# Smoother.net
KiCad netlist of a schematic drawn in EAGLE
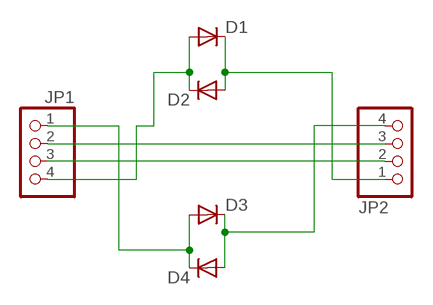
[diagram p0: schematic, sheet 1]

(export (version "E")
  (design (tool "Eeschema 10.0.6"))
  (components
    (comp (ref "D1")
      (value "DIODE_ES1J")
      (footprint "eagle-import:DO214AC")
      (libsource (lib "eagle-import") (part "DIODE_ES1J"))
    )
    (comp (ref "D2")
      (value "DIODE_ES1J")
      (footprint "eagle-import:DO214AC")
      (libsource (lib "eagle-import") (part "DIODE_ES1J"))
    )
    (comp (ref "D3")
      (value "DIODE_ES1J")
      (footprint "eagle-import:DO214AC")
      (libsource (lib "eagle-import") (part "DIODE_ES1J"))
    )
    (comp (ref "D4")
      (value "DIODE_ES1J")
      (footprint "eagle-import:DO214AC")
      (libsource (lib "eagle-import") (part "DIODE_ES1J"))
    )
    (comp (ref "JP1")
      (value "PINHD-1X4/90")
      (footprint "eagle-import:1X04_90")
      (libsource (lib "eagle-import") (part "PINHD-1X4/90"))
    )
    (comp (ref "JP2")
      (value "PINHD-1X4/90")
      (footprint "eagle-import:1X04_90")
      (libsource (lib "eagle-import") (part "PINHD-1X4/90"))
    )
  )
  (nets
    (net (code "1") (name "Net-(D1-PadA)") (class "Default")
      (node (ref "D1") (pin "A") (pinfunction "A_A") (pintype "passive"))
      (node (ref "D2") (pin "C") (pinfunction "C_C") (pintype "passive"))
      (node (ref "JP1") (pin "4") (pinfunction "4_4") (pintype "passive"))
    )
    (net (code "2") (name "Net-(D1-PadC)") (class "Default")
      (node (ref "D1") (pin "C") (pinfunction "C_C") (pintype "passive"))
      (node (ref "D2") (pin "A") (pinfunction "A_A") (pintype "passive"))
      (node (ref "JP2") (pin "1") (pinfunction "1_1") (pintype "passive"))
    )
    (net (code "3") (name "Net-(D3-PadA)") (class "Default")
      (node (ref "D3") (pin "A") (pinfunction "A_A") (pintype "passive"))
      (node (ref "D4") (pin "C") (pinfunction "C_C") (pintype "passive"))
      (node (ref "JP1") (pin "1") (pinfunction "1_1") (pintype "passive"))
    )
    (net (code "4") (name "Net-(D3-PadC)") (class "Default")
      (node (ref "D3") (pin "C") (pinfunction "C_C") (pintype "passive"))
      (node (ref "D4") (pin "A") (pinfunction "A_A") (pintype "passive"))
      (node (ref "JP2") (pin "4") (pinfunction "4_4") (pintype "passive"))
    )
    (net (code "5") (name "Net-(JP1-Pad2)") (class "Default")
      (node (ref "JP1") (pin "2") (pinfunction "2_2") (pintype "passive"))
      (node (ref "JP2") (pin "3") (pinfunction "3_3") (pintype "passive"))
    )
    (net (code "6") (name "Net-(JP1-Pad3)") (class "Default")
      (node (ref "JP1") (pin "3") (pinfunction "3_3") (pintype "passive"))
      (node (ref "JP2") (pin "2") (pinfunction "2_2") (pintype "passive"))
    )
  )
)
